# Main_V1_1.net
KiCad netlist of a schematic drawn in Altium Designer
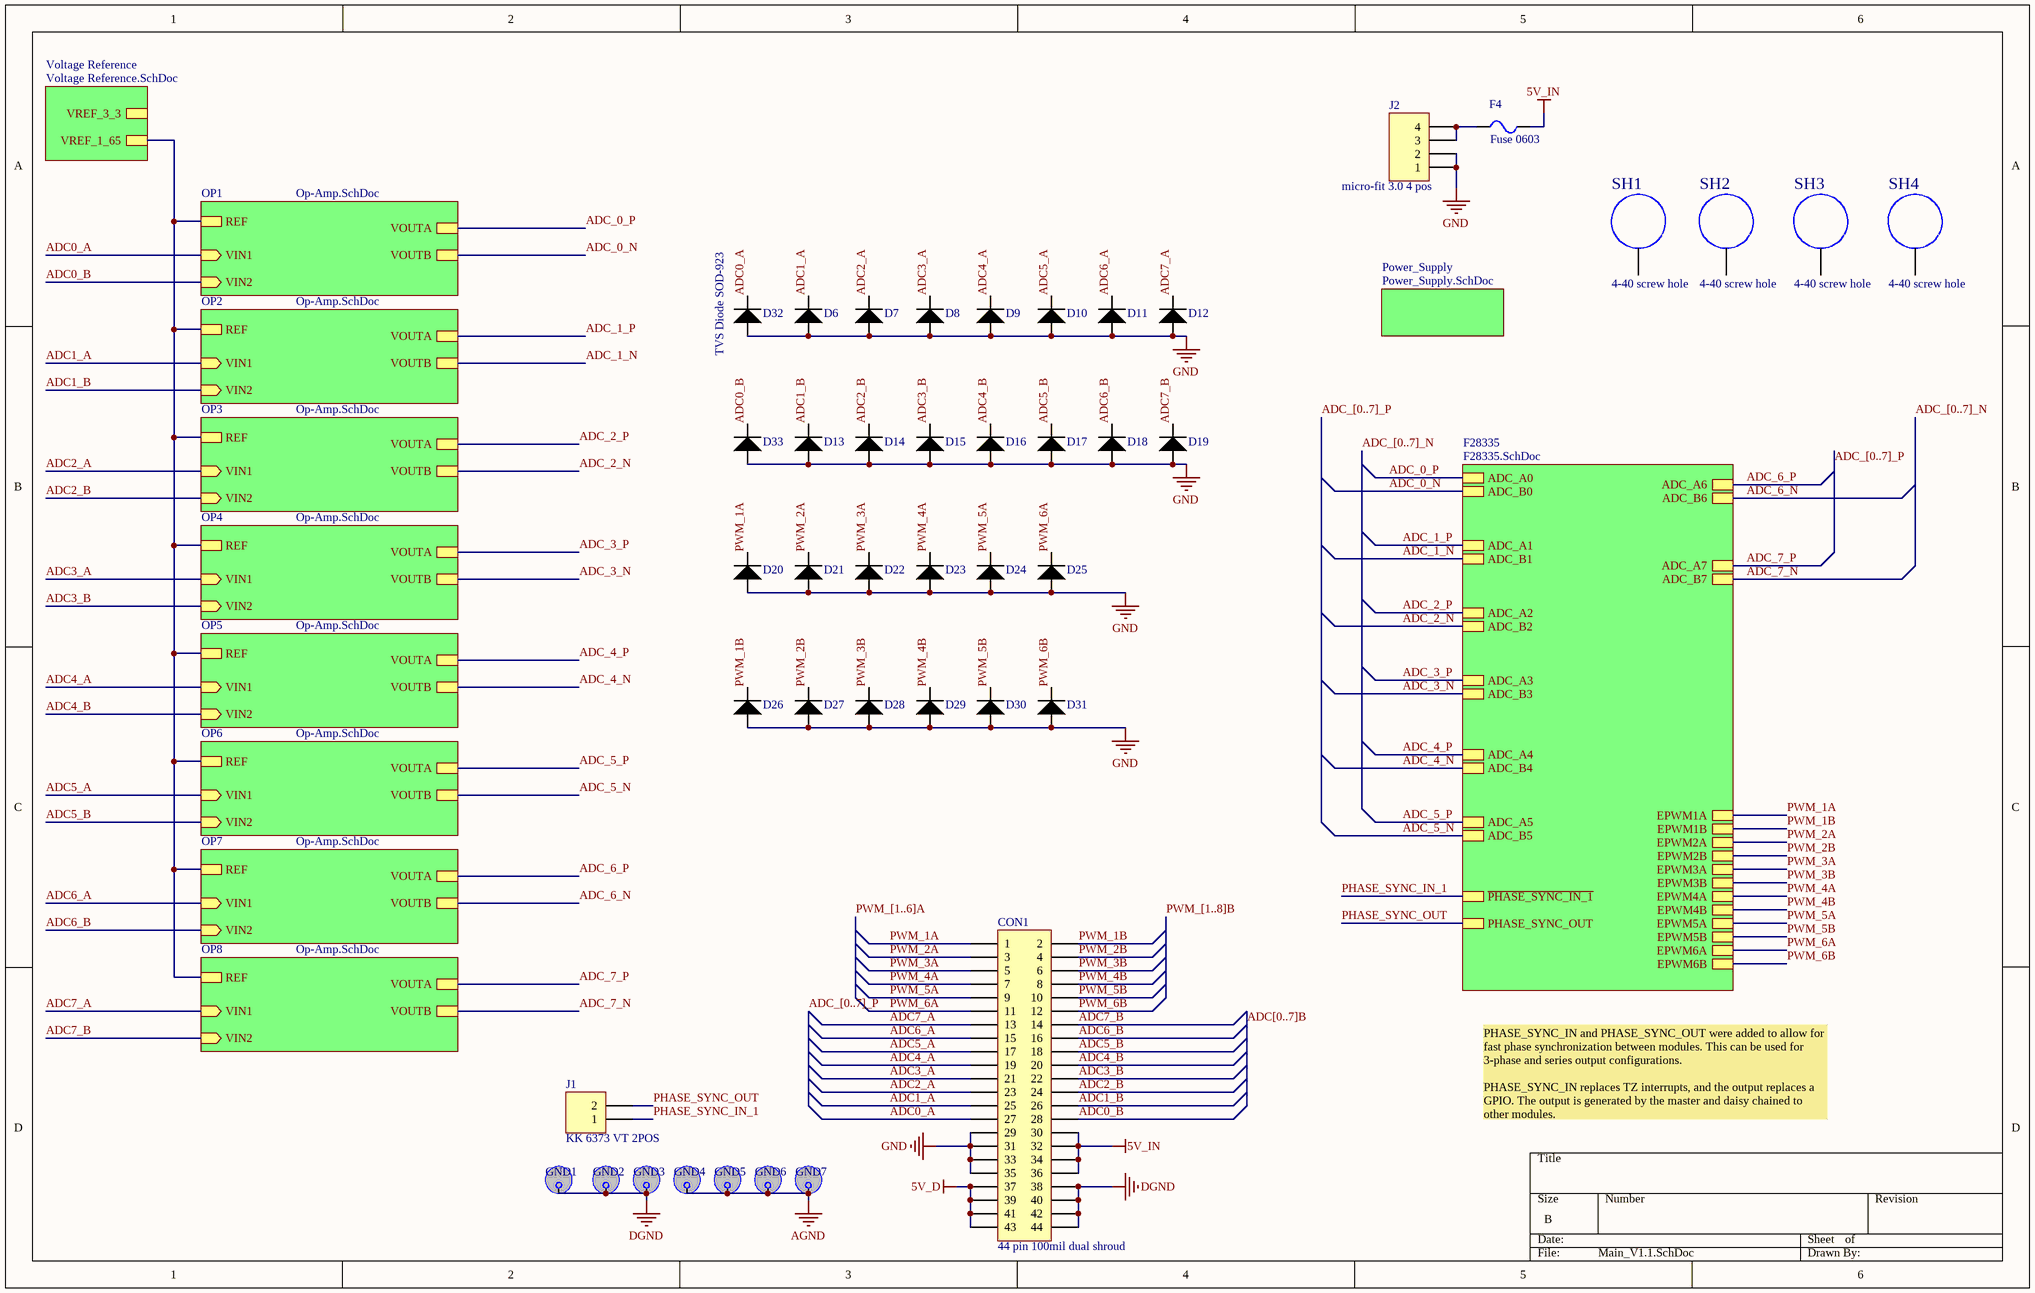
[diagram p0: Main_V1.1.SchDoc]

(export (version "E")
  (design (tool "Eeschema 10.0.6"))
  (components
    (comp (ref "CON1")
      (value "44 pin 100mil dual shroud")
      (footprint "44 PIN 100 MIL DUAL UNSHROUD")
      (description "44 pin 100mil dual unshrouded header")
      (libsource (lib "Aarons_Library") (part "44 pin 100mil dual shroud_1_1_1"))
    )
    (comp (ref "D6")
      (value "TVS Diode SOD-923")
      (footprint "SOD-923-2")
      (libsource (lib "Power_Inductor&Diode_V1.0") (part "TVS Diode SOD-923"))
    )
    (comp (ref "D7")
      (value "TVS Diode SOD-923")
      (footprint "SOD-923-2")
      (libsource (lib "Power_Inductor&Diode_V1.0") (part "TVS Diode SOD-923"))
    )
    (comp (ref "D8")
      (value "TVS Diode SOD-923")
      (footprint "SOD-923-2")
      (libsource (lib "Power_Inductor&Diode_V1.0") (part "TVS Diode SOD-923"))
    )
    (comp (ref "D9")
      (value "TVS Diode SOD-923")
      (footprint "SOD-923-2")
      (libsource (lib "Power_Inductor&Diode_V1.0") (part "TVS Diode SOD-923"))
    )
    (comp (ref "D10")
      (value "TVS Diode SOD-923")
      (footprint "SOD-923-2")
      (libsource (lib "Power_Inductor&Diode_V1.0") (part "TVS Diode SOD-923"))
    )
    (comp (ref "D11")
      (value "TVS Diode SOD-923")
      (footprint "SOD-923-2")
      (libsource (lib "Power_Inductor&Diode_V1.0") (part "TVS Diode SOD-923"))
    )
    (comp (ref "D12")
      (value "TVS Diode SOD-923")
      (footprint "SOD-923-2")
      (libsource (lib "Power_Inductor&Diode_V1.0") (part "TVS Diode SOD-923"))
    )
    (comp (ref "D13")
      (value "TVS Diode SOD-923")
      (footprint "SOD-923-2")
      (libsource (lib "Power_Inductor&Diode_V1.0") (part "TVS Diode SOD-923"))
    )
    (comp (ref "D14")
      (value "TVS Diode SOD-923")
      (footprint "SOD-923-2")
      (libsource (lib "Power_Inductor&Diode_V1.0") (part "TVS Diode SOD-923"))
    )
    (comp (ref "D15")
      (value "TVS Diode SOD-923")
      (footprint "SOD-923-2")
      (libsource (lib "Power_Inductor&Diode_V1.0") (part "TVS Diode SOD-923"))
    )
    (comp (ref "D16")
      (value "TVS Diode SOD-923")
      (footprint "SOD-923-2")
      (libsource (lib "Power_Inductor&Diode_V1.0") (part "TVS Diode SOD-923"))
    )
    (comp (ref "D17")
      (value "TVS Diode SOD-923")
      (footprint "SOD-923-2")
      (libsource (lib "Power_Inductor&Diode_V1.0") (part "TVS Diode SOD-923"))
    )
    (comp (ref "D18")
      (value "TVS Diode SOD-923")
      (footprint "SOD-923-2")
      (libsource (lib "Power_Inductor&Diode_V1.0") (part "TVS Diode SOD-923"))
    )
    (comp (ref "D19")
      (value "TVS Diode SOD-923")
      (footprint "SOD-923-2")
      (libsource (lib "Power_Inductor&Diode_V1.0") (part "TVS Diode SOD-923"))
    )
    (comp (ref "D20")
      (value "TVS Diode SOD-923")
      (footprint "SOD-923-2")
      (libsource (lib "Power_Inductor&Diode_V1.0") (part "TVS Diode SOD-923"))
    )
    (comp (ref "D21")
      (value "TVS Diode SOD-923")
      (footprint "SOD-923-2")
      (libsource (lib "Power_Inductor&Diode_V1.0") (part "TVS Diode SOD-923"))
    )
    (comp (ref "D22")
      (value "TVS Diode SOD-923")
      (footprint "SOD-923-2")
      (libsource (lib "Power_Inductor&Diode_V1.0") (part "TVS Diode SOD-923"))
    )
    (comp (ref "D23")
      (value "TVS Diode SOD-923")
      (footprint "SOD-923-2")
      (libsource (lib "Power_Inductor&Diode_V1.0") (part "TVS Diode SOD-923"))
    )
    (comp (ref "D24")
      (value "TVS Diode SOD-923")
      (footprint "SOD-923-2")
      (libsource (lib "Power_Inductor&Diode_V1.0") (part "TVS Diode SOD-923"))
    )
    (comp (ref "D25")
      (value "TVS Diode SOD-923")
      (footprint "SOD-923-2")
      (libsource (lib "Power_Inductor&Diode_V1.0") (part "TVS Diode SOD-923"))
    )
    (comp (ref "D26")
      (value "TVS Diode SOD-923")
      (footprint "SOD-923-2")
      (libsource (lib "Power_Inductor&Diode_V1.0") (part "TVS Diode SOD-923"))
    )
    (comp (ref "D27")
      (value "TVS Diode SOD-923")
      (footprint "SOD-923-2")
      (libsource (lib "Power_Inductor&Diode_V1.0") (part "TVS Diode SOD-923"))
    )
    (comp (ref "D28")
      (value "TVS Diode SOD-923")
      (footprint "SOD-923-2")
      (libsource (lib "Power_Inductor&Diode_V1.0") (part "TVS Diode SOD-923"))
    )
    (comp (ref "D29")
      (value "TVS Diode SOD-923")
      (footprint "SOD-923-2")
      (libsource (lib "Power_Inductor&Diode_V1.0") (part "TVS Diode SOD-923"))
    )
    (comp (ref "D30")
      (value "TVS Diode SOD-923")
      (footprint "SOD-923-2")
      (libsource (lib "Power_Inductor&Diode_V1.0") (part "TVS Diode SOD-923"))
    )
    (comp (ref "D31")
      (value "TVS Diode SOD-923")
      (footprint "SOD-923-2")
      (libsource (lib "Power_Inductor&Diode_V1.0") (part "TVS Diode SOD-923"))
    )
    (comp (ref "D32")
      (value "TVS Diode SOD-923")
      (footprint "SOD-923-2")
      (libsource (lib "Power_Inductor&Diode_V1.0") (part "TVS Diode SOD-923"))
    )
    (comp (ref "D33")
      (value "TVS Diode SOD-923")
      (footprint "SOD-923-2")
      (libsource (lib "Power_Inductor&Diode_V1.0") (part "TVS Diode SOD-923"))
    )
    (comp (ref "F4")
      (value "Fuse 0603")
      (footprint "RES1608N")
      (libsource (lib "SMD_R&C_V1.0") (part "Fuse 0603"))
    )
    (comp (ref "GND1")
      (value "*")
      (footprint "Keystone 5000")
      (libsource (lib "Aarons_Library") (part "TEST_POINT_HOOK"))
    )
    (comp (ref "GND2")
      (value "*")
      (footprint "Keystone 5000")
      (libsource (lib "Aarons_Library") (part "TEST_POINT_HOOK"))
    )
    (comp (ref "GND3")
      (value "*")
      (footprint "Keystone 5000")
      (libsource (lib "Aarons_Library") (part "TEST_POINT_HOOK"))
    )
    (comp (ref "GND4")
      (value "*")
      (footprint "Keystone 5000")
      (libsource (lib "Aarons_Library") (part "TEST_POINT_HOOK"))
    )
    (comp (ref "GND5")
      (value "*")
      (footprint "Keystone 5000")
      (libsource (lib "Aarons_Library") (part "TEST_POINT_HOOK"))
    )
    (comp (ref "GND6")
      (value "*")
      (footprint "Keystone 5000")
      (libsource (lib "Aarons_Library") (part "TEST_POINT_HOOK"))
    )
    (comp (ref "GND7")
      (value "*")
      (footprint "Keystone 5000")
      (libsource (lib "Aarons_Library") (part "TEST_POINT_HOOK"))
    )
    (comp (ref "J1")
      (value "KK 6373 VT 2POS")
      (footprint "KK 6373 VT 2POS")
      (description "1x2 Locking Header")
      (fields (field (name "PART#") "WM4202-ND"))
      (libsource (lib "Connectors_V1.0") (part "KK 6373 VT 2POS"))
    )
    (comp (ref "J2")
      (value "micro-fit 3.0 4 pos")
      (footprint "micro-fit 3.0 4 pos dual line")
      (fields (field (name "PART#") "43045-0402"))
      (libsource (lib "Connectors_V1.0") (part "micro-fit 3.0 4 poS"))
    )
    (comp (ref "SH1")
      (value "4-40 screw hole")
      (footprint "4-40 screw hole")
      (libsource (lib "Connectors_V1.0") (part "4-40 screw hole"))
    )
    (comp (ref "SH2")
      (value "4-40 screw hole")
      (footprint "4-40 screw hole")
      (libsource (lib "Connectors_V1.0") (part "4-40 screw hole"))
    )
    (comp (ref "SH3")
      (value "4-40 screw hole")
      (footprint "4-40 screw hole")
      (libsource (lib "Connectors_V1.0") (part "4-40 screw hole"))
    )
    (comp (ref "SH4")
      (value "4-40 screw hole")
      (footprint "4-40 screw hole")
      (libsource (lib "Connectors_V1.0") (part "4-40 screw hole"))
    )
  )
  (nets
    (net (code "6") (name "/ADC0_A") (class "Default")
      (node (ref "CON1") (pin "27") (pinfunction "27_27") (pintype "passive"))
      (node (ref "D32") (pin "1") (pinfunction "C_1") (pintype "passive"))
    )
    (net (code "7") (name "/ADC0_B") (class "Default")
      (node (ref "CON1") (pin "28") (pinfunction "28_28") (pintype "passive"))
      (node (ref "D33") (pin "1") (pinfunction "C_1") (pintype "passive"))
    )
    (net (code "8") (name "/ADC1_A") (class "Default")
      (node (ref "CON1") (pin "25") (pinfunction "25_25") (pintype "passive"))
      (node (ref "D6") (pin "1") (pinfunction "C_1") (pintype "passive"))
    )
    (net (code "9") (name "/ADC1_B") (class "Default")
      (node (ref "CON1") (pin "26") (pinfunction "26_26") (pintype "passive"))
      (node (ref "D13") (pin "1") (pinfunction "C_1") (pintype "passive"))
    )
    (net (code "10") (name "/ADC2_A") (class "Default")
      (node (ref "CON1") (pin "23") (pinfunction "23_23") (pintype "passive"))
      (node (ref "D7") (pin "1") (pinfunction "C_1") (pintype "passive"))
    )
    (net (code "11") (name "/ADC2_B") (class "Default")
      (node (ref "CON1") (pin "24") (pinfunction "24_24") (pintype "passive"))
      (node (ref "D14") (pin "1") (pinfunction "C_1") (pintype "passive"))
    )
    (net (code "12") (name "/ADC3_A") (class "Default")
      (node (ref "CON1") (pin "21") (pinfunction "21_21") (pintype "passive"))
      (node (ref "D8") (pin "1") (pinfunction "C_1") (pintype "passive"))
    )
    (net (code "13") (name "/ADC3_B") (class "Default")
      (node (ref "CON1") (pin "22") (pinfunction "22_22") (pintype "passive"))
      (node (ref "D15") (pin "1") (pinfunction "C_1") (pintype "passive"))
    )
    (net (code "14") (name "/ADC4_A") (class "Default")
      (node (ref "CON1") (pin "19") (pinfunction "19_19") (pintype "passive"))
      (node (ref "D9") (pin "1") (pinfunction "C_1") (pintype "passive"))
    )
    (net (code "15") (name "/ADC4_B") (class "Default")
      (node (ref "CON1") (pin "20") (pinfunction "20_20") (pintype "passive"))
      (node (ref "D16") (pin "1") (pinfunction "C_1") (pintype "passive"))
    )
    (net (code "16") (name "/ADC5_A") (class "Default")
      (node (ref "CON1") (pin "17") (pinfunction "17_17") (pintype "passive"))
      (node (ref "D10") (pin "1") (pinfunction "C_1") (pintype "passive"))
    )
    (net (code "17") (name "/ADC5_B") (class "Default")
      (node (ref "CON1") (pin "18") (pinfunction "18_18") (pintype "passive"))
      (node (ref "D17") (pin "1") (pinfunction "C_1") (pintype "passive"))
    )
    (net (code "18") (name "/ADC6_A") (class "Default")
      (node (ref "CON1") (pin "15") (pinfunction "15_15") (pintype "passive"))
      (node (ref "D11") (pin "1") (pinfunction "C_1") (pintype "passive"))
    )
    (net (code "19") (name "/ADC6_B") (class "Default")
      (node (ref "CON1") (pin "16") (pinfunction "16_16") (pintype "passive"))
      (node (ref "D18") (pin "1") (pinfunction "C_1") (pintype "passive"))
    )
    (net (code "20") (name "/ADC7_A") (class "Default")
      (node (ref "CON1") (pin "13") (pinfunction "13_13") (pintype "passive"))
      (node (ref "D12") (pin "1") (pinfunction "C_1") (pintype "passive"))
    )
    (net (code "21") (name "/ADC7_B") (class "Default")
      (node (ref "CON1") (pin "14") (pinfunction "14_14") (pintype "passive"))
      (node (ref "D19") (pin "1") (pinfunction "C_1") (pintype "passive"))
    )
    (net (code "38") (name "/PHASE_SYNC_IN_1") (class "Default")
      (node (ref "J1") (pin "1") (pinfunction "1_1") (pintype "passive"))
    )
    (net (code "39") (name "/PHASE_SYNC_OUT") (class "Default")
      (node (ref "J1") (pin "2") (pinfunction "2_2") (pintype "passive"))
    )
    (net (code "40") (name "/PWM_1A") (class "Default")
      (node (ref "CON1") (pin "1") (pinfunction "1_1") (pintype "passive"))
      (node (ref "D20") (pin "1") (pinfunction "C_1") (pintype "passive"))
    )
    (net (code "41") (name "/PWM_1B") (class "Default")
      (node (ref "CON1") (pin "2") (pinfunction "2_2") (pintype "passive"))
      (node (ref "D26") (pin "1") (pinfunction "C_1") (pintype "passive"))
    )
    (net (code "42") (name "/PWM_2A") (class "Default")
      (node (ref "CON1") (pin "3") (pinfunction "3_3") (pintype "passive"))
      (node (ref "D21") (pin "1") (pinfunction "C_1") (pintype "passive"))
    )
    (net (code "43") (name "/PWM_2B") (class "Default")
      (node (ref "CON1") (pin "4") (pinfunction "4_4") (pintype "passive"))
      (node (ref "D27") (pin "1") (pinfunction "C_1") (pintype "passive"))
    )
    (net (code "44") (name "/PWM_3A") (class "Default")
      (node (ref "CON1") (pin "5") (pinfunction "5_5") (pintype "passive"))
      (node (ref "D22") (pin "1") (pinfunction "C_1") (pintype "passive"))
    )
    (net (code "45") (name "/PWM_3B") (class "Default")
      (node (ref "CON1") (pin "6") (pinfunction "6_6") (pintype "passive"))
      (node (ref "D28") (pin "1") (pinfunction "C_1") (pintype "passive"))
    )
    (net (code "46") (name "/PWM_4A") (class "Default")
      (node (ref "CON1") (pin "7") (pinfunction "7_7") (pintype "passive"))
      (node (ref "D23") (pin "1") (pinfunction "C_1") (pintype "passive"))
    )
    (net (code "47") (name "/PWM_4B") (class "Default")
      (node (ref "CON1") (pin "8") (pinfunction "8_8") (pintype "passive"))
      (node (ref "D29") (pin "1") (pinfunction "C_1") (pintype "passive"))
    )
    (net (code "48") (name "/PWM_5A") (class "Default")
      (node (ref "CON1") (pin "9") (pinfunction "9_9") (pintype "passive"))
      (node (ref "D24") (pin "1") (pinfunction "C_1") (pintype "passive"))
    )
    (net (code "49") (name "/PWM_5B") (class "Default")
      (node (ref "CON1") (pin "10") (pinfunction "10_10") (pintype "passive"))
      (node (ref "D30") (pin "1") (pinfunction "C_1") (pintype "passive"))
    )
    (net (code "50") (name "/PWM_6A") (class "Default")
      (node (ref "CON1") (pin "11") (pinfunction "11_11") (pintype "passive"))
      (node (ref "D25") (pin "1") (pinfunction "C_1") (pintype "passive"))
    )
    (net (code "51") (name "/PWM_6B") (class "Default")
      (node (ref "CON1") (pin "12") (pinfunction "12_12") (pintype "passive"))
      (node (ref "D31") (pin "1") (pinfunction "C_1") (pintype "passive"))
    )
    (net (code "59") (name "5V_D") (class "Default")
      (node (ref "CON1") (pin "37") (pinfunction "37_37") (pintype "passive"))
      (node (ref "CON1") (pin "39") (pinfunction "39_39") (pintype "passive"))
      (node (ref "CON1") (pin "41") (pinfunction "41_41") (pintype "passive"))
      (node (ref "CON1") (pin "43") (pinfunction "43_43") (pintype "passive"))
    )
    (net (code "60") (name "5V_IN") (class "Default")
      (node (ref "CON1") (pin "30") (pinfunction "30_30") (pintype "passive"))
      (node (ref "CON1") (pin "32") (pinfunction "32_32") (pintype "passive"))
      (node (ref "CON1") (pin "34") (pinfunction "34_34") (pintype "passive"))
      (node (ref "CON1") (pin "36") (pinfunction "36_36") (pintype "passive"))
      (node (ref "F4") (pin "2") (pinfunction "2_2") (pintype "passive"))
    )
    (net (code "61") (name "AGND") (class "Default")
      (node (ref "GND4") (pin "1") (pinfunction "1_1") (pintype "passive"))
      (node (ref "GND5") (pin "1") (pinfunction "1_1") (pintype "passive"))
      (node (ref "GND6") (pin "1") (pinfunction "1_1") (pintype "passive"))
      (node (ref "GND7") (pin "1") (pinfunction "1_1") (pintype "passive"))
    )
    (net (code "62") (name "DGND") (class "Default")
      (node (ref "CON1") (pin "38") (pinfunction "38_38") (pintype "passive"))
      (node (ref "CON1") (pin "40") (pinfunction "40_40") (pintype "passive"))
      (node (ref "CON1") (pin "42") (pinfunction "42_42") (pintype "passive"))
      (node (ref "CON1") (pin "44") (pinfunction "44_44") (pintype "passive"))
      (node (ref "GND1") (pin "1") (pinfunction "1_1") (pintype "passive"))
      (node (ref "GND2") (pin "1") (pinfunction "1_1") (pintype "passive"))
      (node (ref "GND3") (pin "1") (pinfunction "1_1") (pintype "passive"))
    )
    (net (code "63") (name "GND") (class "Default")
      (node (ref "CON1") (pin "29") (pinfunction "29_29") (pintype "passive"))
      (node (ref "CON1") (pin "31") (pinfunction "31_31") (pintype "passive"))
      (node (ref "CON1") (pin "33") (pinfunction "33_33") (pintype "passive"))
      (node (ref "CON1") (pin "35") (pinfunction "35_35") (pintype "passive"))
      (node (ref "D10") (pin "2") (pinfunction "A_2") (pintype "passive"))
      (node (ref "D11") (pin "2") (pinfunction "A_2") (pintype "passive"))
      (node (ref "D12") (pin "2") (pinfunction "A_2") (pintype "passive"))
      (node (ref "D13") (pin "2") (pinfunction "A_2") (pintype "passive"))
      (node (ref "D14") (pin "2") (pinfunction "A_2") (pintype "passive"))
      (node (ref "D15") (pin "2") (pinfunction "A_2") (pintype "passive"))
      (node (ref "D16") (pin "2") (pinfunction "A_2") (pintype "passive"))
      (node (ref "D17") (pin "2") (pinfunction "A_2") (pintype "passive"))
      (node (ref "D18") (pin "2") (pinfunction "A_2") (pintype "passive"))
      (node (ref "D19") (pin "2") (pinfunction "A_2") (pintype "passive"))
      (node (ref "D20") (pin "2") (pinfunction "A_2") (pintype "passive"))
      (node (ref "D21") (pin "2") (pinfunction "A_2") (pintype "passive"))
      (node (ref "D22") (pin "2") (pinfunction "A_2") (pintype "passive"))
      (node (ref "D23") (pin "2") (pinfunction "A_2") (pintype "passive"))
      (node (ref "D24") (pin "2") (pinfunction "A_2") (pintype "passive"))
      (node (ref "D25") (pin "2") (pinfunction "A_2") (pintype "passive"))
      (node (ref "D26") (pin "2") (pinfunction "A_2") (pintype "passive"))
      (node (ref "D27") (pin "2") (pinfunction "A_2") (pintype "passive"))
      (node (ref "D28") (pin "2") (pinfunction "A_2") (pintype "passive"))
      (node (ref "D29") (pin "2") (pinfunction "A_2") (pintype "passive"))
      (node (ref "D30") (pin "2") (pinfunction "A_2") (pintype "passive"))
      (node (ref "D31") (pin "2") (pinfunction "A_2") (pintype "passive"))
      (node (ref "D32") (pin "2") (pinfunction "A_2") (pintype "passive"))
      (node (ref "D33") (pin "2") (pinfunction "A_2") (pintype "passive"))
      (node (ref "D6") (pin "2") (pinfunction "A_2") (pintype "passive"))
      (node (ref "D7") (pin "2") (pinfunction "A_2") (pintype "passive"))
      (node (ref "D8") (pin "2") (pinfunction "A_2") (pintype "passive"))
      (node (ref "D9") (pin "2") (pinfunction "A_2") (pintype "passive"))
      (node (ref "J2") (pin "1") (pinfunction "1_1") (pintype "passive"))
      (node (ref "J2") (pin "2") (pinfunction "2_2") (pintype "passive"))
    )
    (net (code "64") (name "Net-(F4-Pad1)") (class "Default")
      (node (ref "F4") (pin "1") (pinfunction "1_1") (pintype "passive"))
      (node (ref "J2") (pin "3") (pinfunction "3_3") (pintype "passive"))
      (node (ref "J2") (pin "4") (pinfunction "4_4") (pintype "passive"))
    )
    (net (code "65") (name "unconnected-(SH1-Pad1)") (class "Default")
      (node (ref "SH1") (pin "1") (pinfunction "1_1") (pintype "passive"))
    )
    (net (code "66") (name "unconnected-(SH2-Pad1)") (class "Default")
      (node (ref "SH2") (pin "1") (pinfunction "1_1") (pintype "passive"))
    )
    (net (code "67") (name "unconnected-(SH3-Pad1)") (class "Default")
      (node (ref "SH3") (pin "1") (pinfunction "1_1") (pintype "passive"))
    )
    (net (code "68") (name "unconnected-(SH4-Pad1)") (class "Default")
      (node (ref "SH4") (pin "1") (pinfunction "1_1") (pintype "passive"))
    )
  )
)
